# untitled.net
KiCad netlist of a schematic drawn in EAGLE
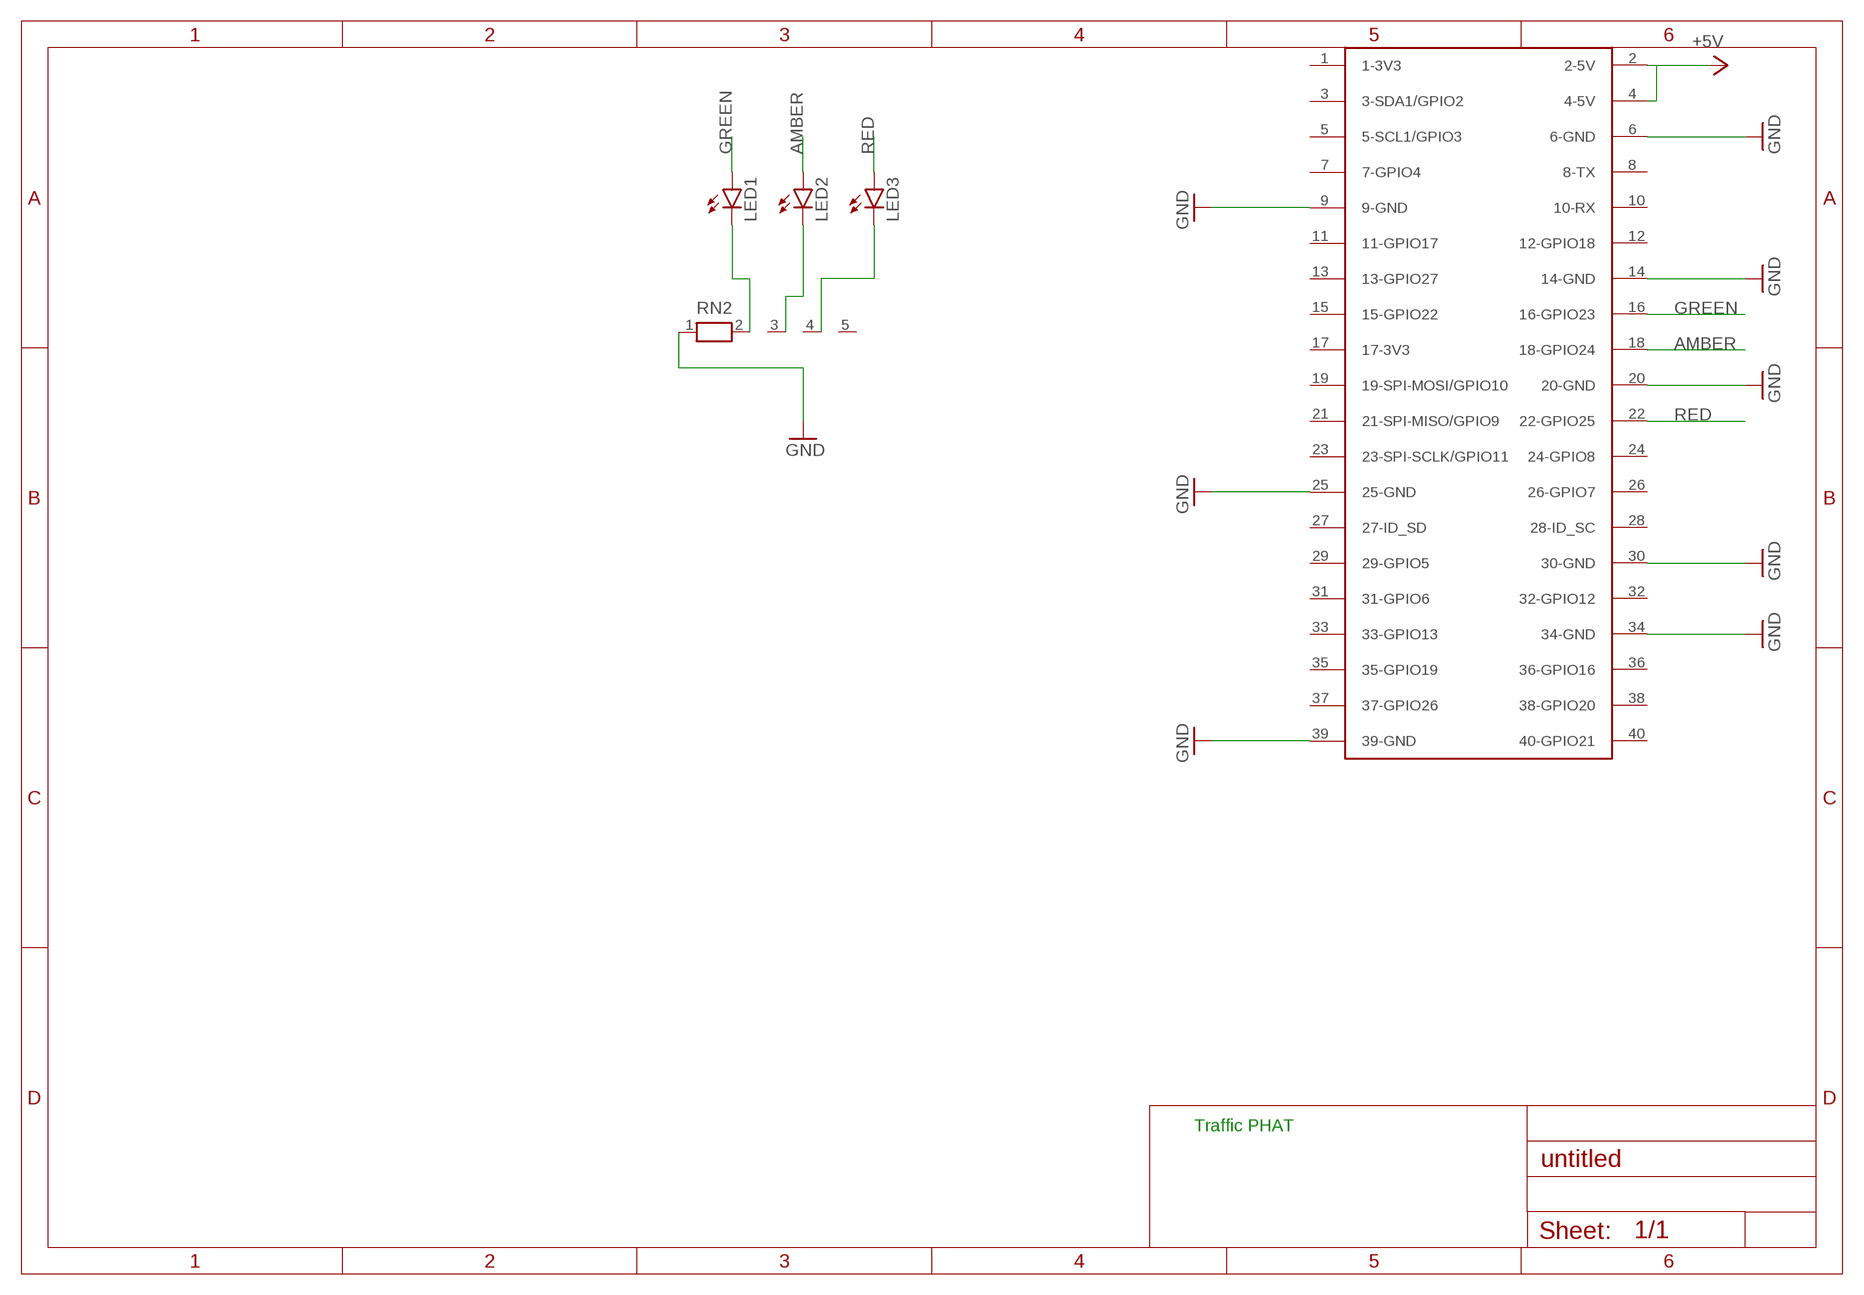
[diagram p0: schematic, sheet 1]

(export (version "E")
  (design (tool "Eeschema 10.0.6"))
  (components
    (comp (ref "LED1")
      (value "LED10MM")
      (footprint "eagle-import:LED10MM")
      (libsource (lib "eagle-import") (part "LED10MM"))
    )
    (comp (ref "LED2")
      (value "LED10MM")
      (footprint "eagle-import:LED10MM")
      (libsource (lib "eagle-import") (part "LED10MM"))
    )
    (comp (ref "LED3")
      (value "LED10MM")
      (footprint "eagle-import:LED10MM")
      (libsource (lib "eagle-import") (part "LED10MM"))
    )
    (comp (ref "RN2")
      (value "RN04")
      (footprint "eagle-import:RN-5")
      (libsource (lib "eagle-import") (part "RN04"))
    )
    (comp (ref "U$1")
      (value "RASPBERRY-PI+HEADERONLY")
      (footprint "eagle-import:RASPBERRY-PI-PLUS-HEADERONLY")
      (libsource (lib "eagle-import") (part "RASPBERRY-PI+HEADERONLY"))
    )
  )
  (nets
    (net (code "1") (name "+5V") (class "Default")
      (node (ref "U$1") (pin "2") (pinfunction "2-5V_2") (pintype "bidirectional"))
      (node (ref "U$1") (pin "4") (pinfunction "4-5V_4") (pintype "bidirectional"))
    )
    (net (code "2") (name "/AMBER") (class "Default")
      (node (ref "LED2") (pin "A") (pinfunction "A_A") (pintype "passive"))
      (node (ref "U$1") (pin "18") (pinfunction "18-GPIO24_18") (pintype "bidirectional"))
    )
    (net (code "3") (name "/GREEN") (class "Default")
      (node (ref "LED1") (pin "A") (pinfunction "A_A") (pintype "passive"))
      (node (ref "U$1") (pin "16") (pinfunction "16-GPIO23_16") (pintype "bidirectional"))
    )
    (net (code "4") (name "/RED") (class "Default")
      (node (ref "LED3") (pin "A") (pinfunction "A_A") (pintype "passive"))
      (node (ref "U$1") (pin "22") (pinfunction "22-GPIO25_22") (pintype "bidirectional"))
    )
    (net (code "5") (name "GND") (class "Default")
      (node (ref "RN2") (pin "1") (pinfunction "1_1") (pintype "passive"))
      (node (ref "U$1") (pin "14") (pinfunction "14-GND_14") (pintype "bidirectional"))
      (node (ref "U$1") (pin "20") (pinfunction "20-GND_20") (pintype "bidirectional"))
      (node (ref "U$1") (pin "25") (pinfunction "25-GND_25") (pintype "bidirectional"))
      (node (ref "U$1") (pin "30") (pinfunction "30-GND_30") (pintype "bidirectional"))
      (node (ref "U$1") (pin "34") (pinfunction "34-GND_34") (pintype "bidirectional"))
      (node (ref "U$1") (pin "39") (pinfunction "39-GND_39") (pintype "bidirectional"))
      (node (ref "U$1") (pin "6") (pinfunction "6-GND_6") (pintype "bidirectional"))
      (node (ref "U$1") (pin "9") (pinfunction "9-GND_9") (pintype "bidirectional"))
    )
    (net (code "6") (name "Net-(LED1-C)") (class "Default")
      (node (ref "LED1") (pin "K") (pinfunction "C_K") (pintype "passive"))
      (node (ref "RN2") (pin "2") (pinfunction "2_2") (pintype "passive"))
    )
    (net (code "7") (name "Net-(LED2-C)") (class "Default")
      (node (ref "LED2") (pin "K") (pinfunction "C_K") (pintype "passive"))
      (node (ref "RN2") (pin "3") (pinfunction "3_3") (pintype "passive"))
    )
    (net (code "8") (name "Net-(LED3-C)") (class "Default")
      (node (ref "LED3") (pin "K") (pinfunction "C_K") (pintype "passive"))
      (node (ref "RN2") (pin "4") (pinfunction "4_4") (pintype "passive"))
    )
    (net (code "9") (name "unconnected-(RN2-Pad5)") (class "Default")
      (node (ref "RN2") (pin "5") (pinfunction "5_5") (pintype "passive"))
    )
    (net (code "10") (name "unconnected-(U$1-1-3V3-Pad1)") (class "Default")
      (node (ref "U$1") (pin "1") (pinfunction "1-3V3_1") (pintype "bidirectional"))
    )
    (net (code "11") (name "unconnected-(U$1-3-SDA1{slash}GPIO2-Pad3)") (class "Default")
      (node (ref "U$1") (pin "3") (pinfunction "3-SDA1/GPIO2_3") (pintype "bidirectional"))
    )
    (net (code "12") (name "unconnected-(U$1-5-SCL1{slash}GPIO3-Pad5)") (class "Default")
      (node (ref "U$1") (pin "5") (pinfunction "5-SCL1/GPIO3_5") (pintype "bidirectional"))
    )
    (net (code "13") (name "unconnected-(U$1-7-GPIO4-Pad7)") (class "Default")
      (node (ref "U$1") (pin "7") (pinfunction "7-GPIO4_7") (pintype "bidirectional"))
    )
    (net (code "14") (name "unconnected-(U$1-8-TX-Pad8)") (class "Default")
      (node (ref "U$1") (pin "8") (pinfunction "8-TX_8") (pintype "bidirectional"))
    )
    (net (code "15") (name "unconnected-(U$1-10-RX-Pad10)") (class "Default")
      (node (ref "U$1") (pin "10") (pinfunction "10-RX_10") (pintype "bidirectional"))
    )
    (net (code "16") (name "unconnected-(U$1-11-GPIO17-Pad11)") (class "Default")
      (node (ref "U$1") (pin "11") (pinfunction "11-GPIO17_11") (pintype "bidirectional"))
    )
    (net (code "17") (name "unconnected-(U$1-12-GPIO18-Pad12)") (class "Default")
      (node (ref "U$1") (pin "12") (pinfunction "12-GPIO18_12") (pintype "bidirectional"))
    )
    (net (code "18") (name "unconnected-(U$1-13-GPIO27-Pad13)") (class "Default")
      (node (ref "U$1") (pin "13") (pinfunction "13-GPIO27_13") (pintype "bidirectional"))
    )
    (net (code "19") (name "unconnected-(U$1-15-GPIO22-Pad15)") (class "Default")
      (node (ref "U$1") (pin "15") (pinfunction "15-GPIO22_15") (pintype "bidirectional"))
    )
    (net (code "20") (name "unconnected-(U$1-17-3V3-Pad17)") (class "Default")
      (node (ref "U$1") (pin "17") (pinfunction "17-3V3_17") (pintype "bidirectional"))
    )
    (net (code "21") (name "unconnected-(U$1-19-SPI-MOSI{slash}GPIO10-Pad19)") (class "Default")
      (node (ref "U$1") (pin "19") (pinfunction "19-SPI-MOSI/GPIO10_19") (pintype "bidirectional"))
    )
    (net (code "22") (name "unconnected-(U$1-21-SPI-MISO{slash}GPIO9-Pad21)") (class "Default")
      (node (ref "U$1") (pin "21") (pinfunction "21-SPI-MISO/GPIO9_21") (pintype "bidirectional"))
    )
    (net (code "23") (name "unconnected-(U$1-23-SPI-SCLK{slash}GPIO11-Pad23)") (class "Default")
      (node (ref "U$1") (pin "23") (pinfunction "23-SPI-SCLK/GPIO11_23") (pintype "bidirectional"))
    )
    (net (code "24") (name "unconnected-(U$1-24-GPIO8-Pad24)") (class "Default")
      (node (ref "U$1") (pin "24") (pinfunction "24-GPIO8_24") (pintype "bidirectional"))
    )
    (net (code "25") (name "unconnected-(U$1-26-GPIO7-Pad26)") (class "Default")
      (node (ref "U$1") (pin "26") (pinfunction "26-GPIO7_26") (pintype "bidirectional"))
    )
    (net (code "26") (name "unconnected-(U$1-27-ID_SD-Pad27)") (class "Default")
      (node (ref "U$1") (pin "27") (pinfunction "27-ID_SD_27") (pintype "bidirectional"))
    )
    (net (code "27") (name "unconnected-(U$1-28-ID_SC-Pad28)") (class "Default")
      (node (ref "U$1") (pin "28") (pinfunction "28-ID_SC_28") (pintype "bidirectional"))
    )
    (net (code "28") (name "unconnected-(U$1-29-GPIO5-Pad29)") (class "Default")
      (node (ref "U$1") (pin "29") (pinfunction "29-GPIO5_29") (pintype "bidirectional"))
    )
    (net (code "29") (name "unconnected-(U$1-31-GPIO6-Pad31)") (class "Default")
      (node (ref "U$1") (pin "31") (pinfunction "31-GPIO6_31") (pintype "bidirectional"))
    )
    (net (code "30") (name "unconnected-(U$1-32-GPIO12-Pad32)") (class "Default")
      (node (ref "U$1") (pin "32") (pinfunction "32-GPIO12_32") (pintype "bidirectional"))
    )
    (net (code "31") (name "unconnected-(U$1-33-GPIO13-Pad33)") (class "Default")
      (node (ref "U$1") (pin "33") (pinfunction "33-GPIO13_33") (pintype "bidirectional"))
    )
    (net (code "32") (name "unconnected-(U$1-35-GPIO19-Pad35)") (class "Default")
      (node (ref "U$1") (pin "35") (pinfunction "35-GPIO19_35") (pintype "bidirectional"))
    )
    (net (code "33") (name "unconnected-(U$1-36-GPIO16-Pad36)") (class "Default")
      (node (ref "U$1") (pin "36") (pinfunction "36-GPIO16_36") (pintype "bidirectional"))
    )
    (net (code "34") (name "unconnected-(U$1-37-GPIO26-Pad37)") (class "Default")
      (node (ref "U$1") (pin "37") (pinfunction "37-GPIO26_37") (pintype "bidirectional"))
    )
    (net (code "35") (name "unconnected-(U$1-38-GPIO20-Pad38)") (class "Default")
      (node (ref "U$1") (pin "38") (pinfunction "38-GPIO20_38") (pintype "bidirectional"))
    )
    (net (code "36") (name "unconnected-(U$1-40-GPIO21-Pad40)") (class "Default")
      (node (ref "U$1") (pin "40") (pinfunction "40-GPIO21_40") (pintype "bidirectional"))
    )
  )
)
